# FeedbackCC1.net
KiCad netlist of a schematic drawn in Altium Designer
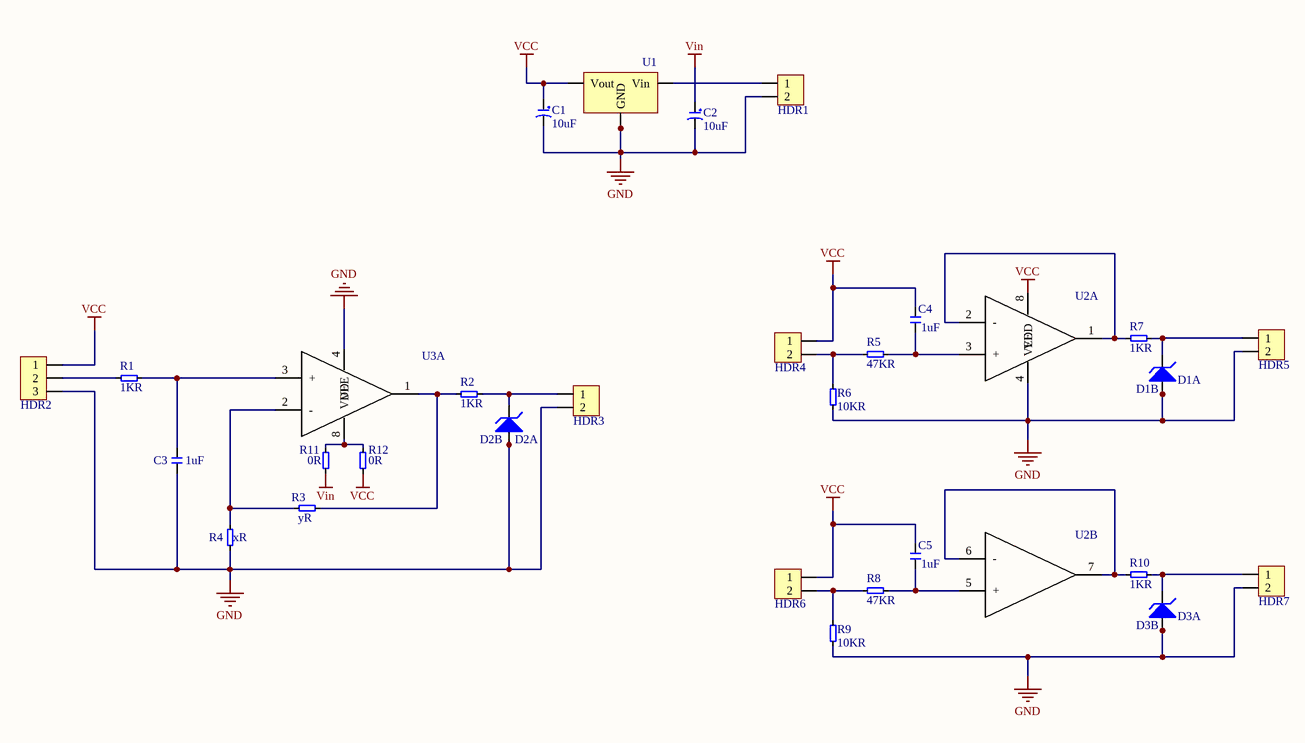
[diagram p0: FeedbackCC1.SchDoc]

(export (version "E")
  (design (tool "Eeschema 10.0.6"))
  (components
    (comp (ref "C1")
      (value "10uF")
      (footprint "C-TANTALUM-CASE-A")
      (description "Capacitor")
      (fields (field (name "TOLERANCE") "x%"))
      (libsource (lib "TG-Lib") (part "Capacitor-2"))
    )
    (comp (ref "C2")
      (value "10uF")
      (footprint "C-TANTALUM-CASE-A")
      (description "Capacitor")
      (fields (field (name "TOLERANCE") "x%"))
      (libsource (lib "TG-Lib") (part "Capacitor-2"))
    )
    (comp (ref "C3")
      (value "1uF")
      (footprint "0603")
      (description "Capacitor")
      (fields (field (name "TOLERANCE") "x%"))
      (libsource (lib "TG-Lib") (part "Capacitor-1"))
    )
    (comp (ref "C4")
      (value "1uF")
      (footprint "0603")
      (description "Capacitor")
      (fields (field (name "TOLERANCE") "x%"))
      (libsource (lib "TG-Lib") (part "Capacitor-1"))
    )
    (comp (ref "C5")
      (value "1uF")
      (footprint "0603")
      (description "Capacitor")
      (fields (field (name "TOLERANCE") "x%"))
      (libsource (lib "TG-Lib") (part "Capacitor-1"))
    )
    (comp (ref "D1")
      (value "D. Zener - SOT23-3 2NC")
      (footprint "SOT-23-3")
      (description "Zener Diode SOT23 - 2NC")
      (fields (field (name "PART") "BZX84C"))
      (libsource (lib "TG-Lib") (part "D. Zener - SOT23-3 2NC"))
    )
    (comp (ref "D2")
      (value "D. Zener - SOT23-3 2NC")
      (footprint "SOT-23-3")
      (description "Zener Diode SOT23 - 2NC")
      (fields (field (name "PART") "BZX84C"))
      (libsource (lib "TG-Lib") (part "D. Zener - SOT23-3 2NC"))
    )
    (comp (ref "D3")
      (value "D. Zener - SOT23-3 2NC")
      (footprint "SOT-23-3")
      (description "Zener Diode SOT23 - 2NC")
      (fields (field (name "PART") "BZX84C"))
      (libsource (lib "TG-Lib") (part "D. Zener - SOT23-3 2NC"))
    )
    (comp (ref "HDR1")
      (value "Header 1x2")
      (footprint "HEADER-1X2-KK")
      (description "Header 1X2")
      (libsource (lib "TG-Lib") (part "Header 1x2"))
    )
    (comp (ref "HDR2")
      (value "Header 1x3")
      (footprint "Header-1x3-KK")
      (description "Header 1X3")
      (libsource (lib "TG-Lib") (part "Header 1x3"))
    )
    (comp (ref "HDR3")
      (value "Header 1x2")
      (footprint "HEADER-1X2-KK")
      (description "Header 1X2")
      (libsource (lib "TG-Lib") (part "Header 1x2"))
    )
    (comp (ref "HDR4")
      (value "Header 1x2")
      (footprint "HEADER-1X2-KK")
      (description "Header 1X2")
      (libsource (lib "") (part "Header 1x2_1"))
    )
    (comp (ref "HDR5")
      (value "Header 1x2")
      (footprint "HEADER-1X2-KK")
      (description "Header 1X2")
      (libsource (lib "TG-Lib") (part "Header 1x2"))
    )
    (comp (ref "HDR6")
      (value "Header 1x2")
      (footprint "HEADER-1X2-KK")
      (description "Header 1X2")
      (libsource (lib "") (part "Header 1x2_1"))
    )
    (comp (ref "HDR7")
      (value "Header 1x2")
      (footprint "HEADER-1X2-KK")
      (description "Header 1X2")
      (libsource (lib "TG-Lib") (part "Header 1x2"))
    )
    (comp (ref "R1")
      (value "1KR")
      (footprint "0603")
      (description "Resistor")
      (fields (field (name "TOLERANCE") "10%"))
      (libsource (lib "TG-Lib") (part "Resistor-1"))
    )
    (comp (ref "R2")
      (value "1KR")
      (footprint "0603")
      (description "Resistor")
      (fields (field (name "TOLERANCE") "10%"))
      (libsource (lib "TG-Lib") (part "Resistor-1"))
    )
    (comp (ref "R3")
      (value "yR")
      (footprint "0603")
      (description "Resistor")
      (fields (field (name "TOLERANCE") "10%"))
      (libsource (lib "TG-Lib") (part "Resistor-1"))
    )
    (comp (ref "R4")
      (value "xR")
      (footprint "0603")
      (description "Resistor")
      (fields (field (name "TOLERANCE") "10%"))
      (libsource (lib "TG-Lib") (part "Resistor-1"))
    )
    (comp (ref "R5")
      (value "47KR")
      (footprint "0603")
      (description "Resistor")
      (fields (field (name "TOLERANCE") "10%"))
      (libsource (lib "TG-Lib") (part "Resistor-1"))
    )
    (comp (ref "R6")
      (value "10KR")
      (footprint "0603")
      (description "Resistor")
      (fields (field (name "TOLERANCE") "10%"))
      (libsource (lib "TG-Lib") (part "Resistor-1"))
    )
    (comp (ref "R7")
      (value "1KR")
      (footprint "0603")
      (description "Resistor")
      (fields (field (name "TOLERANCE") "10%"))
      (libsource (lib "TG-Lib") (part "Resistor-1"))
    )
    (comp (ref "R8")
      (value "47KR")
      (footprint "0603")
      (description "Resistor")
      (fields (field (name "TOLERANCE") "10%"))
      (libsource (lib "TG-Lib") (part "Resistor-1"))
    )
    (comp (ref "R9")
      (value "10KR")
      (footprint "0603")
      (description "Resistor")
      (fields (field (name "TOLERANCE") "10%"))
      (libsource (lib "TG-Lib") (part "Resistor-1"))
    )
    (comp (ref "R10")
      (value "1KR")
      (footprint "0603")
      (description "Resistor")
      (fields (field (name "TOLERANCE") "10%"))
      (libsource (lib "TG-Lib") (part "Resistor-1"))
    )
    (comp (ref "R11")
      (value "0R")
      (footprint "0603")
      (description "Resistor")
      (fields (field (name "TOLERANCE") "10%"))
      (libsource (lib "TG-Lib") (part "Resistor-1"))
    )
    (comp (ref "R12")
      (value "0R")
      (footprint "0603")
      (description "Resistor")
      (fields (field (name "TOLERANCE") "10%"))
      (libsource (lib "TG-Lib") (part "Resistor-1"))
    )
    (comp (ref "U1")
      (value "VoltReg-5V")
      (footprint "SOT-223")
      (description "CI Voltage Regulator 5V")
      (fields (field (name "PART") "AMS1117"))
      (libsource (lib "TG-Lib") (part "VoltReg-5V"))
    )
    (comp (ref "U2")
      (value "AmpOp-2u")
      (footprint "SOIC-8")
      (description "AmpOp Single Supply IC Rail-to-Rail with 2 units")
      (libsource (lib "TG-Lib") (part "AmpOp-2u"))
    )
    (comp (ref "U3")
      (value "AmpOp-2u")
      (footprint "SOIC-8")
      (description "AmpOp Single Supply IC Rail-to-Rail with 2 units")
      (libsource (lib "TG-Lib") (part "AmpOp-2u"))
    )
  )
  (nets
    (net (code "1") (name "GND") (class "Default")
      (node (ref "C1") (pin "2") (pinfunction "2_2") (pintype "passive"))
      (node (ref "C2") (pin "2") (pinfunction "2_2") (pintype "passive"))
      (node (ref "C3") (pin "2") (pinfunction "2_2") (pintype "passive"))
      (node (ref "D1") (pin "1") (pinfunction "1_1") (pintype "passive"))
      (node (ref "D1") (pin "2") (pinfunction "2_2") (pintype "passive"))
      (node (ref "D2") (pin "1") (pinfunction "1_1") (pintype "passive"))
      (node (ref "D2") (pin "2") (pinfunction "2_2") (pintype "passive"))
      (node (ref "D3") (pin "1") (pinfunction "1_1") (pintype "passive"))
      (node (ref "D3") (pin "2") (pinfunction "2_2") (pintype "passive"))
      (node (ref "HDR1") (pin "2") (pinfunction "2_2") (pintype "passive"))
      (node (ref "HDR2") (pin "3") (pinfunction "3_3") (pintype "passive"))
      (node (ref "HDR3") (pin "2") (pinfunction "2_2") (pintype "passive"))
      (node (ref "HDR5") (pin "2") (pinfunction "2_2") (pintype "passive"))
      (node (ref "HDR7") (pin "2") (pinfunction "2_2") (pintype "passive"))
      (node (ref "R4") (pin "1") (pinfunction "1_1") (pintype "passive"))
      (node (ref "R6") (pin "1") (pinfunction "1_1") (pintype "passive"))
      (node (ref "R9") (pin "1") (pinfunction "1_1") (pintype "passive"))
      (node (ref "U1") (pin "0") (pinfunction "0_0") (pintype "passive"))
      (node (ref "U1") (pin "1") (pinfunction "GND_1") (pintype "passive"))
      (node (ref "U2") (pin "4") (pinfunction "VEE_4") (pintype "passive"))
      (node (ref "U3") (pin "4") (pinfunction "VEE_4") (pintype "passive"))
    )
    (net (code "2") (name "Net-(D1-Pad3)") (class "Default")
      (node (ref "D1") (pin "3") (pinfunction "3_3") (pintype "passive"))
      (node (ref "HDR5") (pin "1") (pinfunction "1_1") (pintype "passive"))
      (node (ref "R7") (pin "2") (pinfunction "2_2") (pintype "passive"))
    )
    (net (code "3") (name "Net-(D2-Pad3)") (class "Default")
      (node (ref "D2") (pin "3") (pinfunction "3_3") (pintype "passive"))
      (node (ref "HDR3") (pin "1") (pinfunction "1_1") (pintype "passive"))
      (node (ref "R2") (pin "2") (pinfunction "2_2") (pintype "passive"))
    )
    (net (code "4") (name "Net-(D3-Pad3)") (class "Default")
      (node (ref "D3") (pin "3") (pinfunction "3_3") (pintype "passive"))
      (node (ref "HDR7") (pin "1") (pinfunction "1_1") (pintype "passive"))
      (node (ref "R10") (pin "2") (pinfunction "2_2") (pintype "passive"))
    )
    (net (code "5") (name "Net-(HDR2-Pad2)") (class "Default")
      (node (ref "HDR2") (pin "2") (pinfunction "2_2") (pintype "passive"))
      (node (ref "R1") (pin "1") (pinfunction "1_1") (pintype "passive"))
    )
    (net (code "6") (name "Net-(HDR4-Pad2)") (class "Default")
      (node (ref "HDR4") (pin "2") (pinfunction "2_2") (pintype "passive"))
      (node (ref "R5") (pin "1") (pinfunction "1_1") (pintype "passive"))
      (node (ref "R6") (pin "2") (pinfunction "2_2") (pintype "passive"))
    )
    (net (code "7") (name "Net-(HDR6-Pad2)") (class "Default")
      (node (ref "HDR6") (pin "2") (pinfunction "2_2") (pintype "passive"))
      (node (ref "R8") (pin "1") (pinfunction "1_1") (pintype "passive"))
      (node (ref "R9") (pin "2") (pinfunction "2_2") (pintype "passive"))
    )
    (net (code "8") (name "Net-(U2A-+)") (class "Default")
      (node (ref "C4") (pin "2") (pinfunction "2_2") (pintype "passive"))
      (node (ref "R5") (pin "2") (pinfunction "2_2") (pintype "passive"))
      (node (ref "U2") (pin "3") (pinfunction "+_3") (pintype "passive"))
    )
    (net (code "9") (name "Net-(U2A--)") (class "Default")
      (node (ref "R7") (pin "1") (pinfunction "1_1") (pintype "passive"))
      (node (ref "U2") (pin "1") (pinfunction "NC_1") (pintype "passive"))
      (node (ref "U2") (pin "2") (pinfunction "-_2") (pintype "passive"))
    )
    (net (code "10") (name "Net-(U2B-+)") (class "Default")
      (node (ref "C5") (pin "2") (pinfunction "2_2") (pintype "passive"))
      (node (ref "R8") (pin "2") (pinfunction "2_2") (pintype "passive"))
      (node (ref "U2") (pin "5") (pinfunction "+_5") (pintype "passive"))
    )
    (net (code "11") (name "Net-(U2B--)") (class "Default")
      (node (ref "R10") (pin "1") (pinfunction "1_1") (pintype "passive"))
      (node (ref "U2") (pin "6") (pinfunction "-_6") (pintype "passive"))
      (node (ref "U2") (pin "7") (pinfunction "VDD_7") (pintype "passive"))
    )
    (net (code "12") (name "Net-(U3A-+)") (class "Default")
      (node (ref "C3") (pin "1") (pinfunction "1_1") (pintype "passive"))
      (node (ref "R1") (pin "2") (pinfunction "2_2") (pintype "passive"))
      (node (ref "U3") (pin "3") (pinfunction "+_3") (pintype "passive"))
    )
    (net (code "13") (name "Net-(U3A--)") (class "Default")
      (node (ref "R3") (pin "1") (pinfunction "1_1") (pintype "passive"))
      (node (ref "R4") (pin "2") (pinfunction "2_2") (pintype "passive"))
      (node (ref "U3") (pin "2") (pinfunction "-_2") (pintype "passive"))
    )
    (net (code "14") (name "Net-(U3A-NC)") (class "Default")
      (node (ref "R2") (pin "1") (pinfunction "1_1") (pintype "passive"))
      (node (ref "R3") (pin "2") (pinfunction "2_2") (pintype "passive"))
      (node (ref "U3") (pin "1") (pinfunction "NC_1") (pintype "passive"))
    )
    (net (code "15") (name "Net-(U3A-VDD)") (class "Default")
      (node (ref "R11") (pin "2") (pinfunction "2_2") (pintype "passive"))
      (node (ref "R12") (pin "2") (pinfunction "2_2") (pintype "passive"))
      (node (ref "U3") (pin "8") (pinfunction "VDD_8") (pintype "passive"))
    )
    (net (code "16") (name "VCC") (class "Default")
      (node (ref "C1") (pin "1") (pinfunction "1_1") (pintype "passive"))
      (node (ref "C4") (pin "1") (pinfunction "1_1") (pintype "passive"))
      (node (ref "C5") (pin "1") (pinfunction "1_1") (pintype "passive"))
      (node (ref "HDR2") (pin "1") (pinfunction "1_1") (pintype "passive"))
      (node (ref "HDR4") (pin "1") (pinfunction "1_1") (pintype "passive"))
      (node (ref "HDR6") (pin "1") (pinfunction "1_1") (pintype "passive"))
      (node (ref "R12") (pin "1") (pinfunction "1_1") (pintype "passive"))
      (node (ref "U1") (pin "2") (pinfunction "Vout_2") (pintype "passive"))
      (node (ref "U2") (pin "8") (pinfunction "VDD_8") (pintype "passive"))
    )
    (net (code "17") (name "Vin") (class "Default")
      (node (ref "C2") (pin "1") (pinfunction "1_1") (pintype "passive"))
      (node (ref "HDR1") (pin "1") (pinfunction "1_1") (pintype "passive"))
      (node (ref "R11") (pin "1") (pinfunction "1_1") (pintype "passive"))
      (node (ref "U1") (pin "3") (pinfunction "Vin_3") (pintype "passive"))
    )
  )
)
